# Fuente.net
KiCad netlist of a schematic drawn in Altium Designer
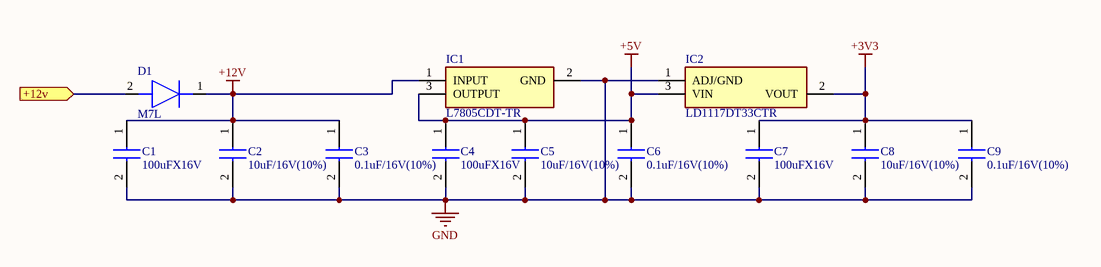
[diagram p0: Fuente.SchDoc]

(export (version "E")
  (design (tool "Eeschema 10.0.6"))
  (components
    (comp (ref "C1")
      (value "100uFX16V")
      (footprint "SamacSys:CAPAE660X550N")
      (description "100UFX16V 20%. 6.3x5.4 ELE.RAD.SMD")
      (fields (field (name "MANUFACTURER_PART_NUMBER") "NACE101M16V6.3X5.5TR13F"))
      (libsource (lib "*") (part "NACE101M16V6.3X5.5TR13F"))
    )
    (comp (ref "C2")
      (value "10uF/16V(10%)")
      (footprint "SamacSys:CAPC3216X100N")
      (description "100NFX50V X7R 10% CER.MULT. SMD 1206")
      (fields
        (field (name "MANUFACTURER_PART_NUMBER") "CL31B104KBCNNNC")
        (field (name "MOUSER PART NUMBER") "187-CL31B104KBCNNNC")
      )
      (libsource (lib "*") (part "CL31B104KBCNNNC"))
    )
    (comp (ref "C3")
      (value "0.1uF/16V(10%)")
      (footprint "SamacSys:CAPC3216X100N")
      (description "100NFX50V X7R 10% CER.MULT. SMD 1206")
      (fields
        (field (name "MANUFACTURER_PART_NUMBER") "CL31B104KBCNNNC")
        (field (name "MOUSER PART NUMBER") "187-CL31B104KBCNNNC")
      )
      (libsource (lib "*") (part "CL31B104KBCNNNC"))
    )
    (comp (ref "C4")
      (value "100uFX16V")
      (footprint "SamacSys:CAPAE660X550N")
      (description "100UFX16V 20%. 6.3x5.4 ELE.RAD.SMD")
      (fields (field (name "MANUFACTURER_PART_NUMBER") "NACE101M16V6.3X5.5TR13F"))
      (libsource (lib "*") (part "NACE101M16V6.3X5.5TR13F"))
    )
    (comp (ref "C5")
      (value "10uF/16V(10%)")
      (footprint "SamacSys:CAPC3216X100N")
      (description "100NFX50V X7R 10% CER.MULT. SMD 1206")
      (fields
        (field (name "MANUFACTURER_PART_NUMBER") "CL31B104KBCNNNC")
        (field (name "MOUSER PART NUMBER") "187-CL31B104KBCNNNC")
      )
      (libsource (lib "*") (part "CL31B104KBCNNNC"))
    )
    (comp (ref "C6")
      (value "0.1uF/16V(10%)")
      (footprint "SamacSys:CAPC3216X100N")
      (description "100NFX50V X7R 10% CER.MULT. SMD 1206")
      (fields
        (field (name "MANUFACTURER_PART_NUMBER") "CL31B104KBCNNNC")
        (field (name "MOUSER PART NUMBER") "187-CL31B104KBCNNNC")
      )
      (libsource (lib "*") (part "CL31B104KBCNNNC"))
    )
    (comp (ref "C7")
      (value "100uFX16V")
      (footprint "SamacSys:CAPAE660X550N")
      (description "100UFX16V 20%. 6.3x5.4 ELE.RAD.SMD")
      (fields (field (name "MANUFACTURER_PART_NUMBER") "NACE101M16V6.3X5.5TR13F"))
      (libsource (lib "*") (part "NACE101M16V6.3X5.5TR13F"))
    )
    (comp (ref "C8")
      (value "10uF/16V(10%)")
      (footprint "SamacSys:CAPC3216X100N")
      (description "100NFX50V X7R 10% CER.MULT. SMD 1206")
      (fields
        (field (name "MANUFACTURER_PART_NUMBER") "CL31B104KBCNNNC")
        (field (name "MOUSER PART NUMBER") "187-CL31B104KBCNNNC")
      )
      (libsource (lib "*") (part "CL31B104KBCNNNC"))
    )
    (comp (ref "C9")
      (value "0.1uF/16V(10%)")
      (footprint "SamacSys:CAPC3216X100N")
      (description "100NFX50V X7R 10% CER.MULT. SMD 1206")
      (fields
        (field (name "MANUFACTURER_PART_NUMBER") "CL31B104KBCNNNC")
        (field (name "MOUSER PART NUMBER") "187-CL31B104KBCNNNC")
      )
      (libsource (lib "*") (part "CL31B104KBCNNNC"))
    )
    (comp (ref "D1")
      (value "M7L")
      (footprint "SamacSys:DIONM5327X240N")
      (description "Diode")
      (fields (field (name "MOUSER PART NUMBER") "637-M7L"))
      (libsource (lib "*") (part "M7L"))
    )
    (comp (ref "IC1")
      (value "L7805CDT-TR")
      (footprint "SamacSys:L7805CDTTR")
      (description "Integrated Circuit")
      (fields (field (name "MOUSER PART NUMBER") "511-L7805CDT-TR"))
      (libsource (lib "SamacSys") (part "L7805CDT-TR"))
    )
    (comp (ref "IC2")
      (value "LD1117DT33CTR")
      (footprint "CPU FPS-400 2022:L7805CDTTR")
      (description "TO-252-3/DPACK 0.95A 3.3V")
      (fields (field (name "MOUSER PART NUMBER") "511-LD1117DT33C-TR"))
      (libsource (lib "*") (part "LD1117DT33CTR"))
    )
  )
  (nets
    (net (code "1") (name "+3V3") (class "Default")
      (node (ref "C7") (pin "1") (pinfunction "+_1") (pintype "passive"))
      (node (ref "C8") (pin "1") (pinfunction "1_1") (pintype "passive"))
      (node (ref "C9") (pin "1") (pinfunction "1_1") (pintype "passive"))
      (node (ref "IC2") (pin "2") (pinfunction "VOUT_2") (pintype "passive"))
    )
    (net (code "2") (name "+5V") (class "Default")
      (node (ref "C4") (pin "1") (pinfunction "+_1") (pintype "passive"))
      (node (ref "C5") (pin "1") (pinfunction "1_1") (pintype "passive"))
      (node (ref "C6") (pin "1") (pinfunction "1_1") (pintype "passive"))
      (node (ref "IC1") (pin "3") (pinfunction "OUTPUT_3") (pintype "passive"))
      (node (ref "IC2") (pin "3") (pinfunction "VIN_3") (pintype "passive"))
    )
    (net (code "3") (name "+12V") (class "Default")
      (node (ref "C1") (pin "1") (pinfunction "+_1") (pintype "passive"))
      (node (ref "C2") (pin "1") (pinfunction "1_1") (pintype "passive"))
      (node (ref "C3") (pin "1") (pinfunction "1_1") (pintype "passive"))
      (node (ref "D1") (pin "1") (pinfunction "K_1") (pintype "passive"))
      (node (ref "IC1") (pin "1") (pinfunction "INPUT_1") (pintype "passive"))
    )
    (net (code "4") (name "/+12v") (class "Default")
      (node (ref "D1") (pin "2") (pinfunction "A_2") (pintype "passive"))
    )
    (net (code "5") (name "GND") (class "Default")
      (node (ref "C1") (pin "2") (pinfunction "-_2") (pintype "passive"))
      (node (ref "C2") (pin "2") (pinfunction "2_2") (pintype "passive"))
      (node (ref "C3") (pin "2") (pinfunction "2_2") (pintype "passive"))
      (node (ref "C4") (pin "2") (pinfunction "-_2") (pintype "passive"))
      (node (ref "C5") (pin "2") (pinfunction "2_2") (pintype "passive"))
      (node (ref "C6") (pin "2") (pinfunction "2_2") (pintype "passive"))
      (node (ref "C7") (pin "2") (pinfunction "-_2") (pintype "passive"))
      (node (ref "C8") (pin "2") (pinfunction "2_2") (pintype "passive"))
      (node (ref "C9") (pin "2") (pinfunction "2_2") (pintype "passive"))
      (node (ref "IC1") (pin "2") (pinfunction "GND_2") (pintype "passive"))
      (node (ref "IC2") (pin "1") (pinfunction "ADJ/GND_1") (pintype "passive"))
    )
  )
)
